# PowerBoard.net
KiCad netlist of a schematic drawn in EAGLE
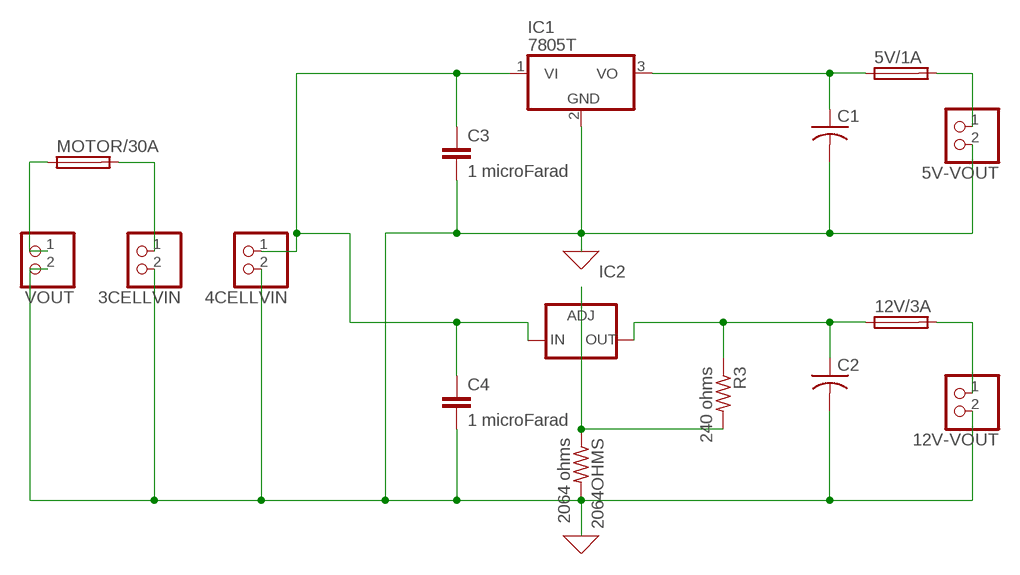
[diagram p0: schematic, sheet 1]

(export (version "E")
  (design (tool "Eeschema 10.0.6"))
  (components
    (comp (ref "3CELLVIN")
      (value "JST_2PIN-THM")
      (footprint "eagle-import:JST-PH-2-THM")
      (libsource (lib "eagle-import") (part "JST_2PIN-THM"))
    )
    (comp (ref "4CELLVIN")
      (value "JST_2PIN-THM")
      (footprint "eagle-import:JST-PH-2-THM")
      (libsource (lib "eagle-import") (part "JST_2PIN-THM"))
    )
    (comp (ref "5V-VOUT")
      (value "JST_2PIN-THM")
      (footprint "eagle-import:JST-PH-2-THM")
      (libsource (lib "eagle-import") (part "JST_2PIN-THM"))
    )
    (comp (ref "5V/1A")
      (value "GSH15")
      (footprint "eagle-import:GSH15")
      (fields (field (name "MPN") "64900001039"))
      (libsource (lib "eagle-import") (part "GSH15"))
    )
    (comp (ref "12V-VOUT")
      (value "JST_2PIN-THM")
      (footprint "eagle-import:JST-PH-2-THM")
      (libsource (lib "eagle-import") (part "JST_2PIN-THM"))
    )
    (comp (ref "12V/3A")
      (value "GSH15")
      (footprint "eagle-import:GSH15")
      (fields (field (name "MPN") "64900001039"))
      (libsource (lib "eagle-import") (part "GSH15"))
    )
    (comp (ref "2064OHMS")
      (value "2064 ohms")
      (footprint "eagle-import:0805-THM")
      (libsource (lib "eagle-import") (part "FLIPFLOP-RES"))
    )
    (comp (ref "C1")
      (value "C-US050-035X075")
      (footprint "eagle-import:C050-035X075")
      (libsource (lib "eagle-import") (part "C-US050-035X075"))
    )
    (comp (ref "C2")
      (value "C-US050-035X075")
      (footprint "eagle-import:C050-035X075")
      (libsource (lib "eagle-import") (part "C-US050-035X075"))
    )
    (comp (ref "C3")
      (value "1 microFarad")
      (footprint "eagle-import:C5B2.5")
      (libsource (lib "eagle-import") (part "C5/2.5"))
    )
    (comp (ref "C4")
      (value "1 microFarad")
      (footprint "eagle-import:C5B2.5")
      (libsource (lib "eagle-import") (part "C5/2.5"))
    )
    (comp (ref "IC1")
      (value "7805T")
      (footprint "eagle-import:TO220H")
      (libsource (lib "eagle-import") (part "78T05"))
    )
    (comp (ref "IC2")
      (value "LM337TS")
      (footprint "eagle-import:337TS")
      (libsource (lib "eagle-import") (part "LM337TS"))
    )
    (comp (ref "MOTOR/30A")
      (value "GSH15")
      (footprint "eagle-import:GSH15")
      (fields (field (name "MPN") "64900001039"))
      (libsource (lib "eagle-import") (part "GSH15"))
    )
    (comp (ref "R3")
      (value "240 ohms")
      (footprint "eagle-import:0805-THM")
      (libsource (lib "eagle-import") (part "FLIPFLOP-RES"))
    )
    (comp (ref "VOUT")
      (value "JST_2PIN-THM")
      (footprint "eagle-import:JST-PH-2-THM")
      (libsource (lib "eagle-import") (part "JST_2PIN-THM"))
    )
  )
  (nets
    (net (code "1") (name "GND") (class "Default")
      (node (ref "12V-VOUT") (pin "2") (pinfunction "1_2") (pintype "passive"))
      (node (ref "2064OHMS") (pin "2") (pinfunction "2_2") (pintype "passive"))
      (node (ref "3CELLVIN") (pin "2") (pinfunction "1_2") (pintype "passive"))
      (node (ref "4CELLVIN") (pin "2") (pinfunction "1_2") (pintype "passive"))
      (node (ref "5V-VOUT") (pin "2") (pinfunction "1_2") (pintype "passive"))
      (node (ref "C1") (pin "2") (pinfunction "2_2") (pintype "passive"))
      (node (ref "C2") (pin "2") (pinfunction "2_2") (pintype "passive"))
      (node (ref "C3") (pin "2") (pinfunction "2_2") (pintype "passive"))
      (node (ref "C4") (pin "2") (pinfunction "2_2") (pintype "passive"))
      (node (ref "IC1") (pin "2") (pinfunction "GND_2") (pintype "passive"))
      (node (ref "VOUT") (pin "2") (pinfunction "1_2") (pintype "passive"))
    )
    (net (code "2") (name "Net-(3CELLVIN-2)") (class "Default")
      (node (ref "3CELLVIN") (pin "1") (pinfunction "2_1") (pintype "passive"))
      (node (ref "MOTOR/30A") (pin "2") (pinfunction "2_2") (pintype "passive"))
    )
    (net (code "3") (name "Net-(4CELLVIN-2)") (class "Default")
      (node (ref "4CELLVIN") (pin "1") (pinfunction "2_1") (pintype "passive"))
      (node (ref "C3") (pin "1") (pinfunction "1_1") (pintype "passive"))
      (node (ref "C4") (pin "1") (pinfunction "1_1") (pintype "passive"))
      (node (ref "IC1") (pin "1") (pinfunction "VI_1") (pintype "input"))
      (node (ref "IC2") (pin "2") (pinfunction "IN_2") (pintype "input"))
    )
    (net (code "4") (name "Net-(5V-VOUT-2)") (class "Default")
      (node (ref "5V-VOUT") (pin "1") (pinfunction "2_1") (pintype "passive"))
      (node (ref "5V/1A") (pin "2") (pinfunction "2_2") (pintype "passive"))
    )
    (net (code "5") (name "Net-(12V-VOUT-2)") (class "Default")
      (node (ref "12V-VOUT") (pin "1") (pinfunction "2_1") (pintype "passive"))
      (node (ref "12V/3A") (pin "2") (pinfunction "2_2") (pintype "passive"))
    )
    (net (code "6") (name "Net-(IC1-VO)") (class "Default")
      (node (ref "5V/1A") (pin "1") (pinfunction "1_1") (pintype "passive"))
      (node (ref "C1") (pin "1") (pinfunction "1_1") (pintype "passive"))
      (node (ref "IC1") (pin "3") (pinfunction "VO_3") (pintype "passive"))
    )
    (net (code "7") (name "Net-(IC2-ADJ)") (class "Default")
      (node (ref "2064OHMS") (pin "1") (pinfunction "1_1") (pintype "passive"))
      (node (ref "IC2") (pin "1") (pinfunction "ADJ_1") (pintype "input"))
      (node (ref "R3") (pin "2") (pinfunction "2_2") (pintype "passive"))
    )
    (net (code "8") (name "Net-(IC2-OUT)") (class "Default")
      (node (ref "12V/3A") (pin "1") (pinfunction "1_1") (pintype "passive"))
      (node (ref "C2") (pin "1") (pinfunction "1_1") (pintype "passive"))
      (node (ref "IC2") (pin "3") (pinfunction "OUT_3") (pintype "passive"))
      (node (ref "R3") (pin "1") (pinfunction "1_1") (pintype "passive"))
    )
    (net (code "9") (name "Net-(VOUT-2)") (class "Default")
      (node (ref "MOTOR/30A") (pin "1") (pinfunction "1_1") (pintype "passive"))
      (node (ref "VOUT") (pin "1") (pinfunction "2_1") (pintype "passive"))
    )
  )
)
